# ESP32_with_USBC.net
KiCad netlist of a schematic drawn in Altium Designer
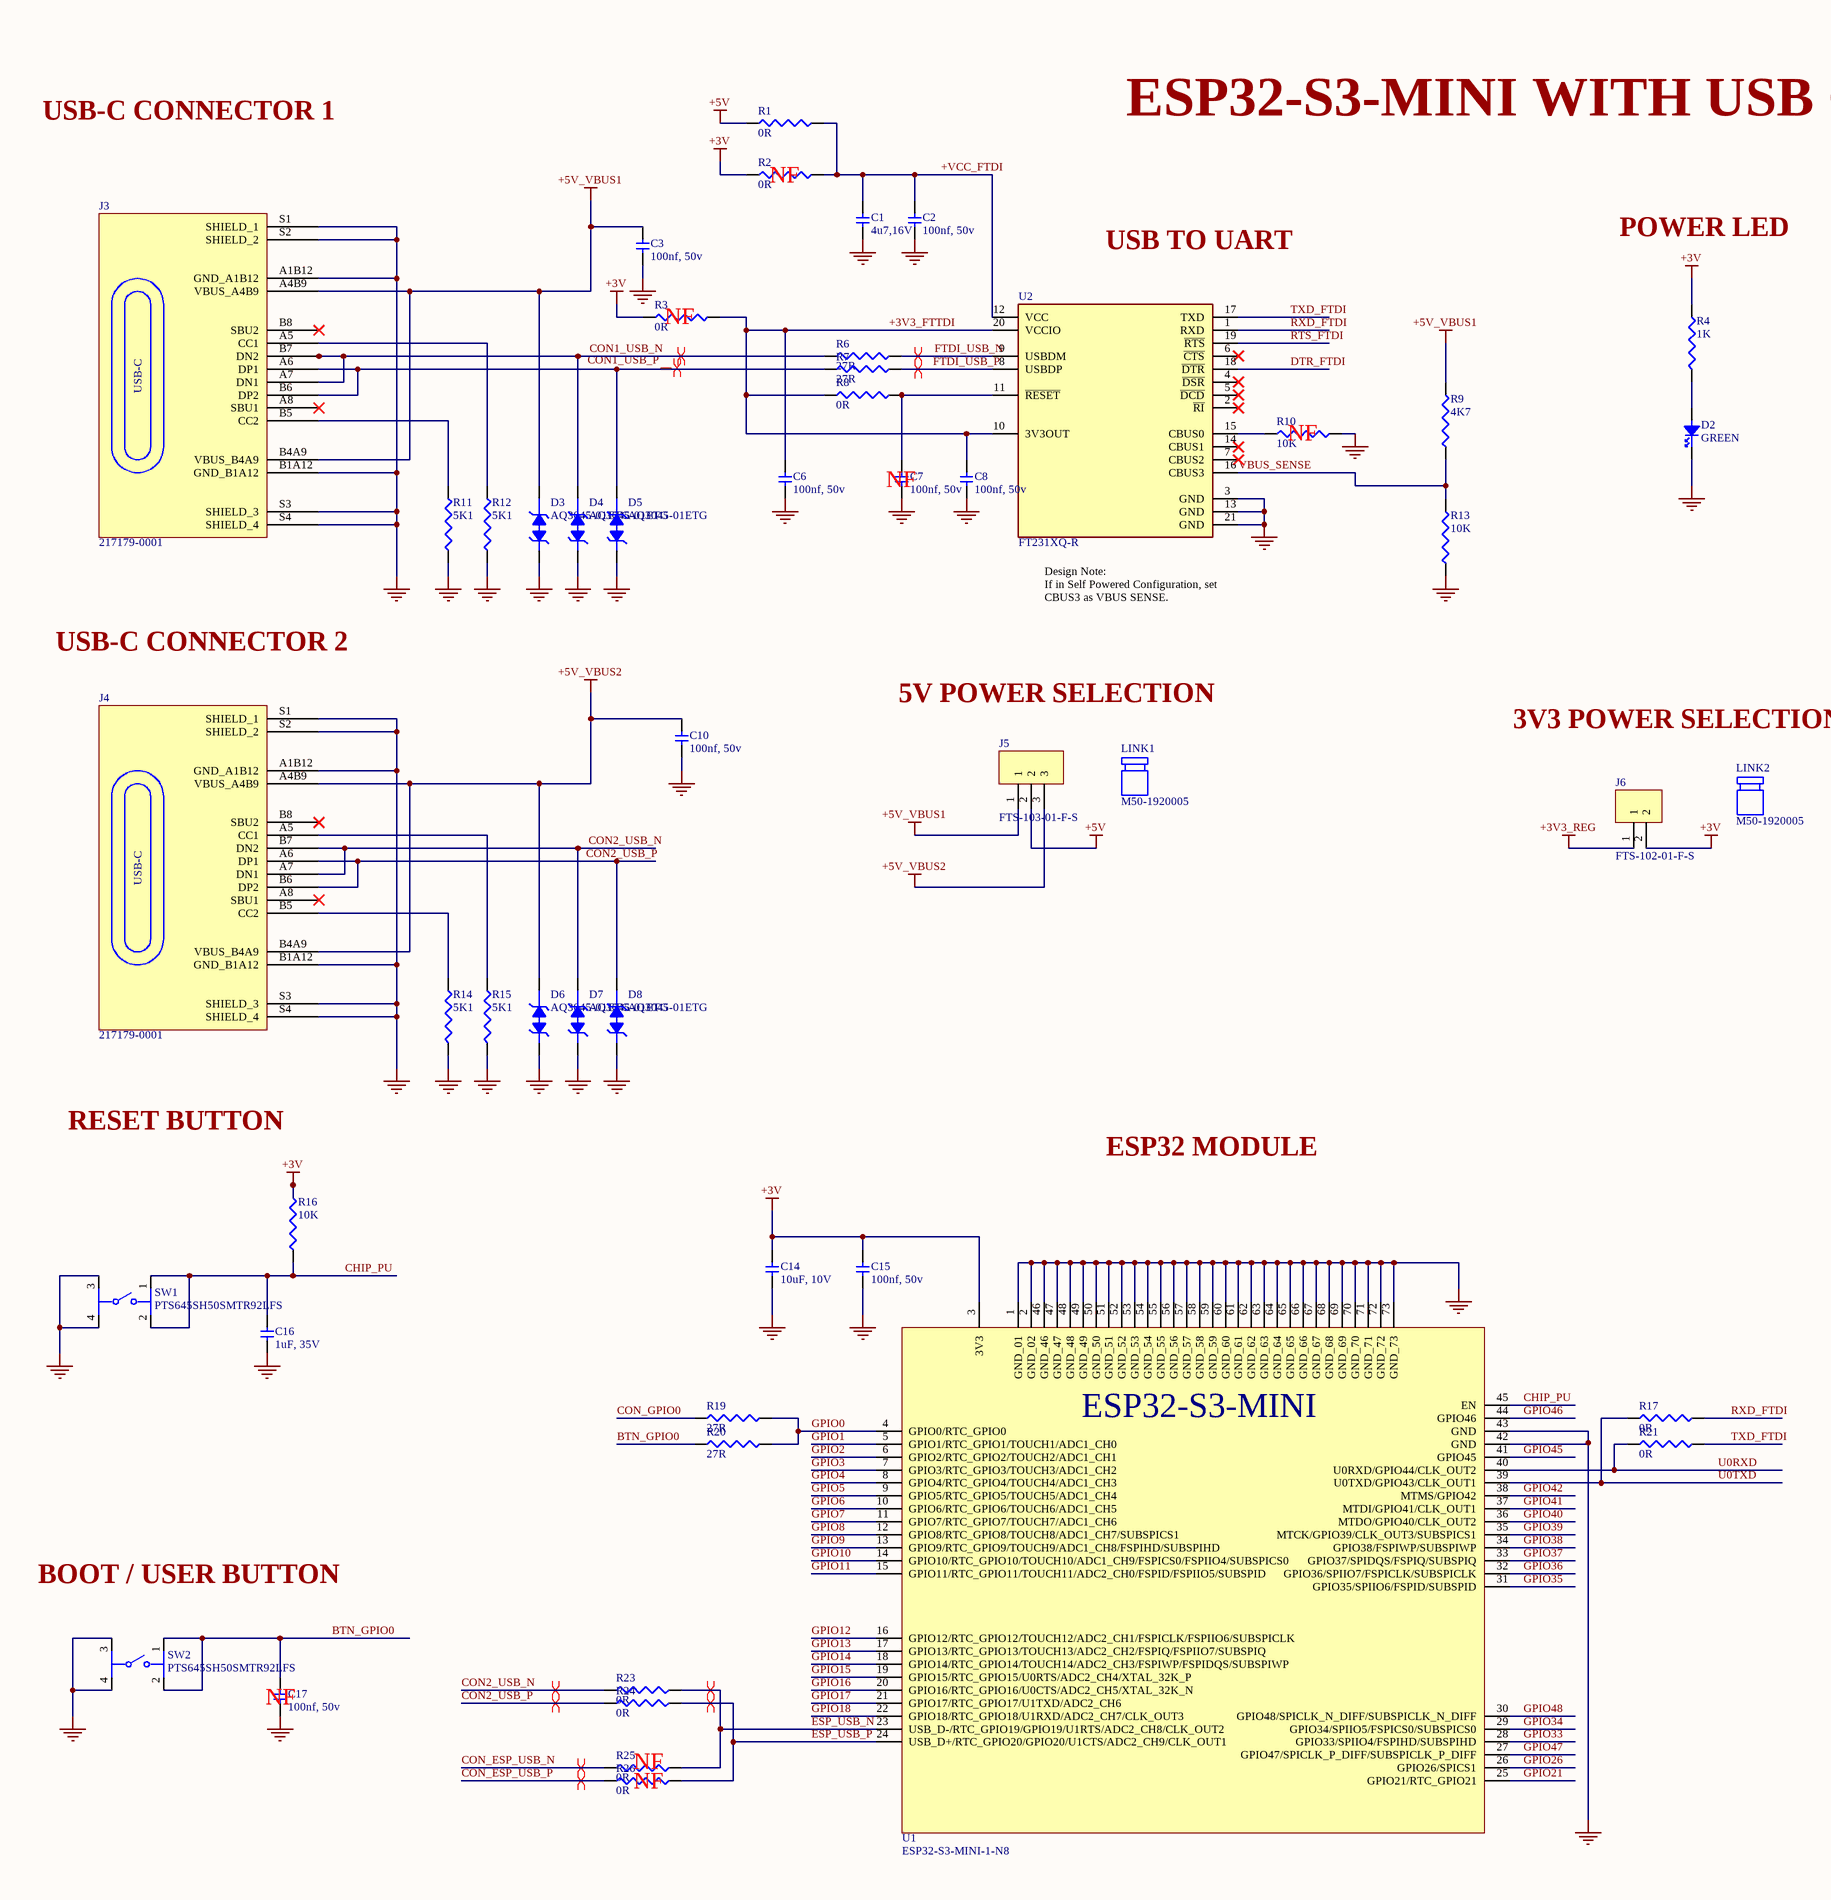
[diagram p0: ESP32 with USBC.SchDoc, left]
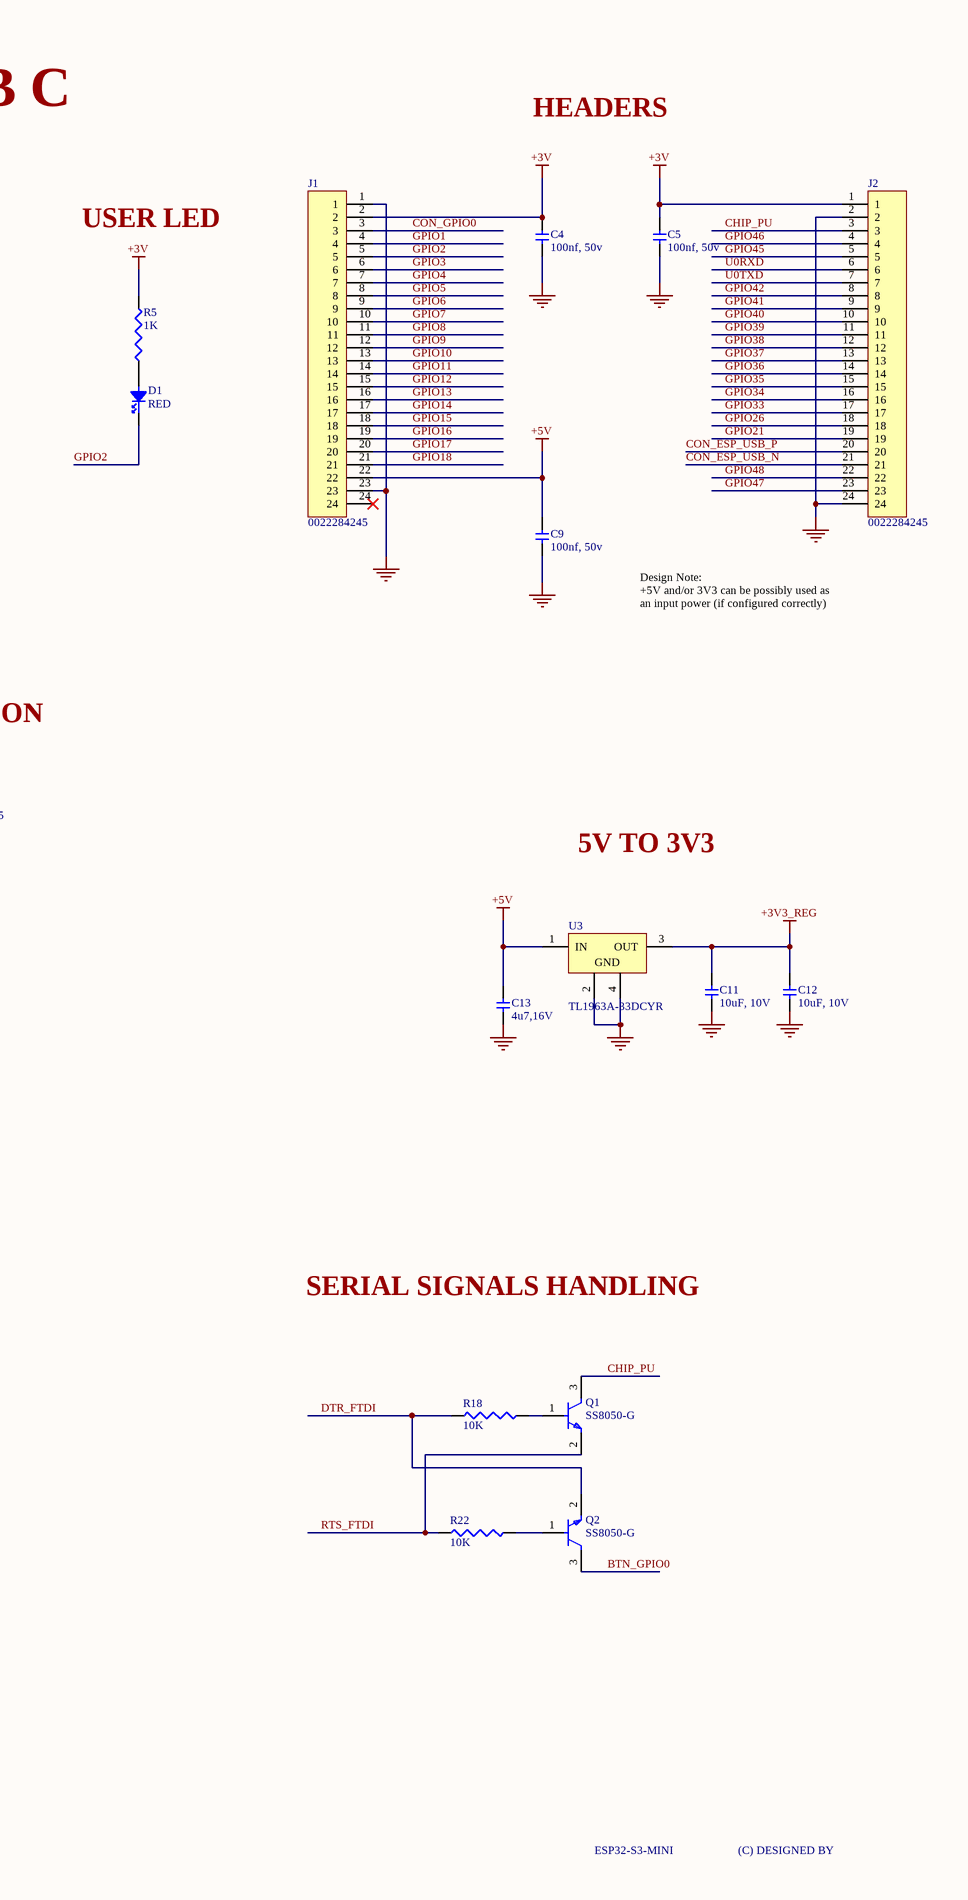
[diagram p1: ESP32 with USBC.SchDoc, right]

(export (version "E")
  (design (tool "Eeschema 10.0.6"))
  (components
    (comp (ref "C1")
      (value "4u7,16V")
      (footprint "CAPC1005X55N")
      (fields
        (field (name "MANUFACTURER") "Samsung")
        (field (name "MANUFACTURER PART NUMBER") "CL05A475MO5NUNC")
        (field (name "LCCS PART NUMBER") "C318563")
      )
      (libsource (lib "Schlib") (part "CL05A475MO5NUNC"))
    )
    (comp (ref "C2")
      (value "100nf, 50v")
      (footprint "CAPC1005X55N")
      (fields
        (field (name "MANUFACTURER") "Samsung")
        (field (name "MANUFACTURER PART NUMBER") "CL05B104KB54PNC")
        (field (name "LCCS PART NUMBER") "C307331")
      )
      (libsource (lib "Schlib") (part "CL05B104KB54PNC"))
    )
    (comp (ref "C3")
      (value "100nf, 50v")
      (footprint "CAPC1005X55N")
      (fields
        (field (name "MANUFACTURER") "Samsung")
        (field (name "MANUFACTURER PART NUMBER") "CL05B104KB54PNC")
        (field (name "LCCS PART NUMBER") "C307331")
      )
      (libsource (lib "Schlib") (part "CL05B104KB54PNC"))
    )
    (comp (ref "C4")
      (value "100nf, 50v")
      (footprint "CAPC1005X55N")
      (fields
        (field (name "MANUFACTURER") "Samsung")
        (field (name "MANUFACTURER PART NUMBER") "CL05B104KB54PNC")
        (field (name "LCCS PART NUMBER") "C307331")
      )
      (libsource (lib "Schlib") (part "CL05B104KB54PNC"))
    )
    (comp (ref "C5")
      (value "100nf, 50v")
      (footprint "CAPC1005X55N")
      (fields
        (field (name "MANUFACTURER") "Samsung")
        (field (name "MANUFACTURER PART NUMBER") "CL05B104KB54PNC")
        (field (name "LCCS PART NUMBER") "C307331")
      )
      (libsource (lib "Schlib") (part "CL05B104KB54PNC"))
    )
    (comp (ref "C6")
      (value "100nf, 50v")
      (footprint "CAPC1005X55N")
      (fields
        (field (name "MANUFACTURER") "Samsung")
        (field (name "MANUFACTURER PART NUMBER") "CL05B104KB54PNC")
        (field (name "LCCS PART NUMBER") "C307331")
      )
      (libsource (lib "Schlib") (part "CL05B104KB54PNC"))
    )
    (comp (ref "C7")
      (value "100nf, 50v")
      (footprint "CAPC1005X55N")
      (fields
        (field (name "MANUFACTURER") "Samsung")
        (field (name "MANUFACTURER PART NUMBER") "CL05B104KB54PNC")
        (field (name "LCCS PART NUMBER") "C307331")
      )
      (libsource (lib "Schlib") (part "CL05B104KB54PNC"))
    )
    (comp (ref "C8")
      (value "100nf, 50v")
      (footprint "CAPC1005X55N")
      (fields
        (field (name "MANUFACTURER") "Samsung")
        (field (name "MANUFACTURER PART NUMBER") "CL05B104KB54PNC")
        (field (name "LCCS PART NUMBER") "C307331")
      )
      (libsource (lib "Schlib") (part "CL05B104KB54PNC"))
    )
    (comp (ref "C9")
      (value "100nf, 50v")
      (footprint "CAPC1005X55N")
      (fields
        (field (name "MANUFACTURER") "Samsung")
        (field (name "MANUFACTURER PART NUMBER") "CL05B104KB54PNC")
        (field (name "LCCS PART NUMBER") "C307331")
      )
      (libsource (lib "Schlib") (part "CL05B104KB54PNC"))
    )
    (comp (ref "C10")
      (value "100nf, 50v")
      (footprint "CAPC1005X55N")
      (fields
        (field (name "MANUFACTURER") "Samsung")
        (field (name "MANUFACTURER PART NUMBER") "CL05B104KB54PNC")
        (field (name "LCCS PART NUMBER") "C307331")
      )
      (libsource (lib "Schlib") (part "CL05B104KB54PNC"))
    )
    (comp (ref "C11")
      (value "10uF, 10V")
      (footprint "CAPC1005X55N")
      (fields
        (field (name "MANUFACTURER") "Samsung")
        (field (name "MANUFACTURER PART NUMBER") "CL05A106MP8NUB8")
        (field (name "LCCS PART NUMBER") "C307415")
      )
      (libsource (lib "Schlib") (part "CL05A106MP8NUB8"))
    )
    (comp (ref "C12")
      (value "10uF, 10V")
      (footprint "CAPC1005X55N")
      (fields
        (field (name "MANUFACTURER") "Samsung")
        (field (name "MANUFACTURER PART NUMBER") "CL05A106MP8NUB8")
        (field (name "LCCS PART NUMBER") "C307415")
      )
      (libsource (lib "Schlib") (part "CL05A106MP8NUB8"))
    )
    (comp (ref "C13")
      (value "4u7,16V")
      (footprint "CAPC1005X55N")
      (fields
        (field (name "MANUFACTURER") "Samsung")
        (field (name "MANUFACTURER PART NUMBER") "CL05A475MO5NUNC")
        (field (name "LCCS PART NUMBER") "C318563")
      )
      (libsource (lib "Schlib") (part "CL05A475MO5NUNC"))
    )
    (comp (ref "C14")
      (value "10uF, 10V")
      (footprint "CAPC1005X55N")
      (fields
        (field (name "MANUFACTURER") "Samsung")
        (field (name "MANUFACTURER PART NUMBER") "CL05A106MP8NUB8")
        (field (name "LCCS PART NUMBER") "C307415")
      )
      (libsource (lib "Schlib") (part "CL05A106MP8NUB8"))
    )
    (comp (ref "C15")
      (value "100nf, 50v")
      (footprint "CAPC1005X55N")
      (fields
        (field (name "MANUFACTURER") "Samsung")
        (field (name "MANUFACTURER PART NUMBER") "CL05B104KB54PNC")
        (field (name "LCCS PART NUMBER") "C307331")
      )
      (libsource (lib "Schlib") (part "CL05B104KB54PNC"))
    )
    (comp (ref "C16")
      (value "1uF, 35V")
      (footprint "CAPC1005X55N")
      (fields
        (field (name "MANUFACTURER") "Samsung")
        (field (name "MANUFACTURER PART NUMBER") "CL05A105KL5NRNC")
        (field (name "LCCS PART NUMBER") "C307413")
      )
      (libsource (lib "Schlib") (part "CL05A105KL5NRNC"))
    )
    (comp (ref "C17")
      (value "100nf, 50v")
      (footprint "CAPC1005X55N")
      (fields
        (field (name "MANUFACTURER") "Samsung")
        (field (name "MANUFACTURER PART NUMBER") "CL05B104KB54PNC")
        (field (name "LCCS PART NUMBER") "C307331")
      )
      (libsource (lib "Schlib") (part "CL05B104KB54PNC"))
    )
    (comp (ref "D1")
      (value "RED")
      (footprint "LED0402R")
      (description "Single Color LED, Super Red, 0.5mm")
      (fields
        (field (name "MANUFACTURER") "Vishay")
        (field (name "MANUFACTURER PART NUMBER") "VLMS1500-GS08")
      )
      (libsource (lib "Schlib") (part "VLMS1500-GS08"))
    )
    (comp (ref "D2")
      (value "GREEN")
      (footprint "LED0402G")
      (description "Single Color LED, Yellow Green, 0.5mm")
      (fields
        (field (name "MANUFACTURER") "Vishay")
        (field (name "MANUFACTURER PART NUMBER") "VLMG1500-GS08")
      )
      (libsource (lib "Schlib") (part "VLMG1500-GS08"))
    )
    (comp (ref "D3")
      (value "AQ3045-01ETG")
      (footprint "SOD882")
      (description "Trans Voltage Suppressor Diode, 40W, 5.3V V(RWM), Bidirectional, 1 Element, Silicon, MO-236")
      (fields (field (name "MANUFACTURER") "Littelfuse") (field (name "LCCS PART NUMBER") "C3710326"))
      (libsource (lib "Schlib") (part "AQ3045-01ETG"))
    )
    (comp (ref "D4")
      (value "AQ3045-01ETG")
      (footprint "SOD882")
      (description "Trans Voltage Suppressor Diode, 40W, 5.3V V(RWM), Bidirectional, 1 Element, Silicon, MO-236")
      (fields (field (name "MANUFACTURER") "Littelfuse") (field (name "LCCS PART NUMBER") "C3710326"))
      (libsource (lib "Schlib") (part "AQ3045-01ETG"))
    )
    (comp (ref "D5")
      (value "AQ3045-01ETG")
      (footprint "SOD882")
      (description "Trans Voltage Suppressor Diode, 40W, 5.3V V(RWM), Bidirectional, 1 Element, Silicon, MO-236")
      (fields (field (name "MANUFACTURER") "Littelfuse") (field (name "LCCS PART NUMBER") "C3710326"))
      (libsource (lib "Schlib") (part "AQ3045-01ETG"))
    )
    (comp (ref "D6")
      (value "AQ3045-01ETG")
      (footprint "SOD882")
      (description "Trans Voltage Suppressor Diode, 40W, 5.3V V(RWM), Bidirectional, 1 Element, Silicon, MO-236")
      (fields (field (name "MANUFACTURER") "Littelfuse") (field (name "LCCS PART NUMBER") "C3710326"))
      (libsource (lib "Schlib") (part "AQ3045-01ETG"))
    )
    (comp (ref "D7")
      (value "AQ3045-01ETG")
      (footprint "SOD882")
      (description "Trans Voltage Suppressor Diode, 40W, 5.3V V(RWM), Bidirectional, 1 Element, Silicon, MO-236")
      (fields (field (name "MANUFACTURER") "Littelfuse") (field (name "LCCS PART NUMBER") "C3710326"))
      (libsource (lib "Schlib") (part "AQ3045-01ETG"))
    )
    (comp (ref "D8")
      (value "AQ3045-01ETG")
      (footprint "SOD882")
      (description "Trans Voltage Suppressor Diode, 40W, 5.3V V(RWM), Bidirectional, 1 Element, Silicon, MO-236")
      (fields (field (name "MANUFACTURER") "Littelfuse") (field (name "LCCS PART NUMBER") "C3710326"))
      (libsource (lib "Schlib") (part "AQ3045-01ETG"))
    )
    (comp (ref "J1")
      (value "0022284245")
      (footprint "HDR_1x24_2.54MM")
      (description "Board Connector, 24 Contact(s), 1 Row(s), Male, Straight, Solder Terminal")
      (fields (field (name "MANUFACTURER") "Molex") (field (name "LCCS PART NUMBER") "C7145888"))
      (libsource (lib "") (part "0022284245_1"))
    )
    (comp (ref "J2")
      (value "0022284245")
      (footprint "HDR_1x24_2.54MM")
      (description "Board Connector, 24 Contact(s), 1 Row(s), Male, Straight, Solder Terminal")
      (fields (field (name "MANUFACTURER") "Molex") (field (name "LCCS PART NUMBER") "C7145888"))
      (libsource (lib "Schlib") (part "0022284245"))
    )
    (comp (ref "J3")
      (value "217179-0001")
      (footprint "FP-2171790001-MFG")
      (description "USB Type C - Connector, Top-mount SMT, 16pos ¦ Molex Incorporated 217179-0001")
      (fields (field (name "MANUFACTURER") "Molex") (field (name "LCCS PART NUMBER") "C3179684"))
      (libsource (lib "Schlib") (part "217179-0001"))
    )
    (comp (ref "J4")
      (value "217179-0001")
      (footprint "FP-2171790001-MFG")
      (description "USB Type C - Connector, Top-mount SMT, 16pos ¦ Molex Incorporated 217179-0001")
      (fields (field (name "MANUFACTURER") "Molex") (field (name "LCCS PART NUMBER") "C3179684"))
      (libsource (lib "Schlib") (part "217179-0001"))
    )
    (comp (ref "J5")
      (value "FTS-103-01-F-S")
      (footprint "HDR_1X3_1.27MM")
      (description "Board Connector, 3 Contact(s), 1 Row(s), Male, Straight, Solder Terminal")
      (fields (field (name "MANUFACTURER") "Samtec") (field (name "LCCS PART NUMBER") "C3333578"))
      (libsource (lib "Schlib") (part "FTS-103-01-F-S"))
    )
    (comp (ref "J6")
      (value "FTS-102-01-F-S")
      (footprint "HDR_1X2_1.27MM")
      (description "Board Connector, 2 Contact(s), 1 Row(s), Male, Straight, Solder Terminal")
      (fields (field (name "MANUFACTURER") "Samtec") (field (name "LCCS PART NUMBER") "C6045317"))
      (libsource (lib "Schlib") (part "FTS-102-01-F-S"))
    )
    (comp (ref "LINK1")
      (value "M50-1920005")
      (description "Interconnection Device")
      (fields (field (name "MANUFACTURER") "Harwin") (field (name "LCCS PART NUMBER") "C6985646"))
      (libsource (lib "Schlib") (part "M50-1920005"))
    )
    (comp (ref "LINK2")
      (value "M50-1920005")
      (description "Interconnection Device")
      (fields (field (name "MANUFACTURER") "Harwin") (field (name "LCCS PART NUMBER") "C6985646"))
      (libsource (lib "Schlib") (part "M50-1920005"))
    )
    (comp (ref "Q1")
      (value "SS8050-G")
      (footprint "FP-SS8050-G-IPC_B")
      (description "Small Signal Bipolar Transistor, 1.5A I(C), 25V V(BR)CEO, 1-Element, NPN, Silicon")
      (fields (field (name "MANUFACTURER") "Comchip") (field (name "LCCS PART NUMBER") "C164886"))
      (libsource (lib "Schlib") (part "SS8050-G"))
    )
    (comp (ref "Q2")
      (value "SS8050-G")
      (footprint "FP-SS8050-G-IPC_B")
      (description "Small Signal Bipolar Transistor, 1.5A I(C), 25V V(BR)CEO, 1-Element, NPN, Silicon")
      (fields (field (name "MANUFACTURER") "Comchip") (field (name "LCCS PART NUMBER") "C164886"))
      (libsource (lib "Schlib") (part "SS8050-G"))
    )
    (comp (ref "R1")
      (value "0R")
      (footprint "RESC1005X37N")
      (description "Metal Glaze/thick Film, 0.0625W, 0ohm, Surface Mount, 0402")
      (fields
        (field (name "MANUFACTURER") "Yageo")
        (field (name "MANUFACTURER PART NUMBER") "RC0402JR-070RL")
      )
      (libsource (lib "Schlib") (part "RC0402JR-070RL"))
    )
    (comp (ref "R2")
      (value "0R")
      (footprint "RESC1005X37N")
      (description "Metal Glaze/thick Film, 0.0625W, 0ohm, Surface Mount, 0402")
      (fields
        (field (name "MANUFACTURER") "Yageo")
        (field (name "MANUFACTURER PART NUMBER") "RC0402JR-070RL")
      )
      (libsource (lib "Schlib") (part "RC0402JR-070RL"))
    )
    (comp (ref "R3")
      (value "0R")
      (footprint "RESC1005X37N")
      (description "Metal Glaze/thick Film, 0.0625W, 0ohm, Surface Mount, 0402")
      (fields
        (field (name "MANUFACTURER") "Yageo")
        (field (name "MANUFACTURER PART NUMBER") "RC0402JR-070RL")
      )
      (libsource (lib "Schlib") (part "RC0402JR-070RL"))
    )
    (comp (ref "R4")
      (value "1K")
      (footprint "RESC1005X37N")
      (fields
        (field (name "MANUFACTURER") "Yageo")
        (field (name "MANUFACTURER PART NUMBER") "RC0402FR-071KL")
        (field (name "TOLERANCE") "1%")
      )
      (libsource (lib "Schlib") (part "RC0402FR-071KL"))
    )
    (comp (ref "R5")
      (value "1K")
      (footprint "RESC1005X37N")
      (fields
        (field (name "MANUFACTURER") "Yageo")
        (field (name "MANUFACTURER PART NUMBER") "RC0402FR-071KL")
        (field (name "TOLERANCE") "1%")
      )
      (libsource (lib "Schlib") (part "RC0402FR-071KL"))
    )
    (comp (ref "R6")
      (value "27R")
      (footprint "RESC1005X37N")
      (fields
        (field (name "MANUFACTURER") "Yageo")
        (field (name "MANUFACTURER PART NUMBER") "RC0402FR-0727RL")
        (field (name "TOLERANCE") "1%")
      )
      (libsource (lib "Schlib") (part "RC0402FR-0727RL"))
    )
    (comp (ref "R7")
      (value "27R")
      (footprint "RESC1005X37N")
      (fields
        (field (name "MANUFACTURER") "Yageo")
        (field (name "MANUFACTURER PART NUMBER") "RC0402FR-0727RL")
        (field (name "TOLERANCE") "1%")
      )
      (libsource (lib "Schlib") (part "RC0402FR-0727RL"))
    )
    (comp (ref "R8")
      (value "0R")
      (footprint "RESC1005X37N")
      (description "Metal Glaze/thick Film, 0.0625W, 0ohm, Surface Mount, 0402")
      (fields
        (field (name "MANUFACTURER") "Yageo")
        (field (name "MANUFACTURER PART NUMBER") "RC0402JR-070RL")
      )
      (libsource (lib "Schlib") (part "RC0402JR-070RL"))
    )
    (comp (ref "R9")
      (value "4K7")
      (footprint "RESC1005X37N")
      (fields
        (field (name "MANUFACTURER") "Yageo")
        (field (name "MANUFACTURER PART NUMBER") "RC0402FR-074K7L")
        (field (name "TOLERANCE") "1%")
      )
      (libsource (lib "Schlib") (part "RC0402FR-074K7L"))
    )
    (comp (ref "R10")
      (value "10K")
      (footprint "RESC1005X37N")
      (fields
        (field (name "MANUFACTURER") "Yageo")
        (field (name "MANUFACTURER PART NUMBER") "AC0402FR-0710KL")
        (field (name "TOLERANCE") "1%")
      )
      (libsource (lib "Schlib") (part "AC0402FR-0710KL"))
    )
    (comp (ref "R11")
      (value "5K1")
      (footprint "RESC1005X37N")
      (fields
        (field (name "MANUFACTURER") "Yageo")
        (field (name "MANUFACTURER PART NUMBER") "AC0402FR-075K1L")
        (field (name "TOLERANCE") "1%")
      )
      (libsource (lib "Schlib") (part "AC0402FR-075K1L"))
    )
    (comp (ref "R12")
      (value "5K1")
      (footprint "RESC1005X37N")
      (fields
        (field (name "MANUFACTURER") "Yageo")
        (field (name "MANUFACTURER PART NUMBER") "AC0402FR-075K1L")
        (field (name "TOLERANCE") "1%")
      )
      (libsource (lib "Schlib") (part "AC0402FR-075K1L"))
    )
    (comp (ref "R13")
      (value "10K")
      (footprint "RESC1005X37N")
      (fields
        (field (name "MANUFACTURER") "Yageo")
        (field (name "MANUFACTURER PART NUMBER") "AC0402FR-0710KL")
        (field (name "TOLERANCE") "1%")
      )
      (libsource (lib "Schlib") (part "AC0402FR-0710KL"))
    )
    (comp (ref "R14")
      (value "5K1")
      (footprint "RESC1005X37N")
      (fields
        (field (name "MANUFACTURER") "Yageo")
        (field (name "MANUFACTURER PART NUMBER") "AC0402FR-075K1L")
        (field (name "TOLERANCE") "1%")
      )
      (libsource (lib "Schlib") (part "AC0402FR-075K1L"))
    )
    (comp (ref "R15")
      (value "5K1")
      (footprint "RESC1005X37N")
      (fields
        (field (name "MANUFACTURER") "Yageo")
        (field (name "MANUFACTURER PART NUMBER") "AC0402FR-075K1L")
        (field (name "TOLERANCE") "1%")
      )
      (libsource (lib "Schlib") (part "AC0402FR-075K1L"))
    )
    (comp (ref "R16")
      (value "10K")
      (footprint "RESC1005X37N")
      (fields
        (field (name "MANUFACTURER") "Yageo")
        (field (name "MANUFACTURER PART NUMBER") "AC0402FR-0710KL")
        (field (name "TOLERANCE") "1%")
      )
      (libsource (lib "Schlib") (part "AC0402FR-0710KL"))
    )
    (comp (ref "R17")
      (value "0R")
      (footprint "RESC1005X37N")
      (description "Metal Glaze/thick Film, 0.0625W, 0ohm, Surface Mount, 0402")
      (fields
        (field (name "MANUFACTURER") "Yageo")
        (field (name "MANUFACTURER PART NUMBER") "RC0402JR-070RL")
      )
      (libsource (lib "Schlib") (part "RC0402JR-070RL"))
    )
    (comp (ref "R18")
      (value "10K")
      (footprint "RESC1005X37N")
      (fields
        (field (name "MANUFACTURER") "Yageo")
        (field (name "MANUFACTURER PART NUMBER") "AC0402FR-0710KL")
        (field (name "TOLERANCE") "1%")
      )
      (libsource (lib "Schlib") (part "AC0402FR-0710KL"))
    )
    (comp (ref "R19")
      (value "27R")
      (footprint "RESC1005X37N")
      (fields
        (field (name "MANUFACTURER") "Yageo")
        (field (name "MANUFACTURER PART NUMBER") "RC0402FR-0727RL")
        (field (name "TOLERANCE") "1%")
      )
      (libsource (lib "Schlib") (part "RC0402FR-0727RL"))
    )
    (comp (ref "R20")
      (value "27R")
      (footprint "RESC1005X37N")
      (fields
        (field (name "MANUFACTURER") "Yageo")
        (field (name "MANUFACTURER PART NUMBER") "RC0402FR-0727RL")
        (field (name "TOLERANCE") "1%")
      )
      (libsource (lib "Schlib") (part "RC0402FR-0727RL"))
    )
    (comp (ref "R21")
      (value "0R")
      (footprint "RESC1005X37N")
      (description "Metal Glaze/thick Film, 0.0625W, 0ohm, Surface Mount, 0402")
      (fields
        (field (name "MANUFACTURER") "Yageo")
        (field (name "MANUFACTURER PART NUMBER") "RC0402JR-070RL")
      )
      (libsource (lib "Schlib") (part "RC0402JR-070RL"))
    )
    (comp (ref "R22")
      (value "10K")
      (footprint "RESC1005X37N")
      (fields
        (field (name "MANUFACTURER") "Yageo")
        (field (name "MANUFACTURER PART NUMBER") "AC0402FR-0710KL")
        (field (name "TOLERANCE") "1%")
      )
      (libsource (lib "Schlib") (part "AC0402FR-0710KL"))
    )
    (comp (ref "R23")
      (value "0R")
      (footprint "RESC1005X37N")
      (description "Metal Glaze/thick Film, 0.0625W, 0ohm, Surface Mount, 0402")
      (fields
        (field (name "MANUFACTURER") "Yageo")
        (field (name "MANUFACTURER PART NUMBER") "RC0402JR-070RL")
      )
      (libsource (lib "Schlib") (part "RC0402JR-070RL"))
    )
    (comp (ref "R24")
      (value "0R")
      (footprint "RESC1005X37N")
      (description "Metal Glaze/thick Film, 0.0625W, 0ohm, Surface Mount, 0402")
      (fields
        (field (name "MANUFACTURER") "Yageo")
        (field (name "MANUFACTURER PART NUMBER") "RC0402JR-070RL")
      )
      (libsource (lib "Schlib") (part "RC0402JR-070RL"))
    )
    (comp (ref "R25")
      (value "0R")
      (footprint "RESC1005X37N")
      (description "Metal Glaze/thick Film, 0.0625W, 0ohm, Surface Mount, 0402")
      (fields
        (field (name "MANUFACTURER") "Yageo")
        (field (name "MANUFACTURER PART NUMBER") "RC0402JR-070RL")
      )
      (libsource (lib "Schlib") (part "RC0402JR-070RL"))
    )
    (comp (ref "R26")
      (value "0R")
      (footprint "RESC1005X37N")
      (description "Metal Glaze/thick Film, 0.0625W, 0ohm, Surface Mount, 0402")
      (fields
        (field (name "MANUFACTURER") "Yageo")
        (field (name "MANUFACTURER PART NUMBER") "RC0402JR-070RL")
      )
      (libsource (lib "Schlib") (part "RC0402JR-070RL"))
    )
    (comp (ref "SW1")
      (value "PTS645SH50SMTR92LFS")
      (footprint "FP-PTS645SH50SMTR92LFS-MFG")
      (fields (field (name "MANUFACTURER") "ITT C&K") (field (name "LCCS PART NUMBER") "C221869"))
      (libsource (lib "Schlib") (part "PTS645SH50SMTR92LFS"))
    )
    (comp (ref "SW2")
      (value "PTS645SH50SMTR92LFS")
      (footprint "FP-PTS645SH50SMTR92LFS-MFG")
      (fields (field (name "MANUFACTURER") "ITT C&K") (field (name "LCCS PART NUMBER") "C221869"))
      (libsource (lib "Schlib") (part "PTS645SH50SMTR92LFS"))
    )
    (comp (ref "U1")
      (value "ESP32-S3-MINI-1-N8")
      (footprint "XCVR_ESP32-S3-MINI-1-N8")
      (description "SMD module, ESP32-S3FN8, 8 MB SPI flash, PCB antenna")
      (fields (field (name "MANUFACTURER") "Espressif Systems") (field (name "LCCS PART NUMBER") "C2913206"))
      (libsource (lib "Schlib") (part "ESP32-S3-MINI-1-N8"))
    )
    (comp (ref "U2")
      (value "FT231XQ-R")
      (footprint "FP-QFN-20-IPC_B")
      (description "Microprocessor Circuit, CMOS")
      (fields (field (name "MANUFACTURER") "FTDI") (field (name "LCCS PART NUMBER") "C132159"))
      (libsource (lib "Schlib") (part "FT231XQ-R"))
    )
    (comp (ref "U3")
      (value "TL1963A-33DCYR")
      (footprint "DCY0004A_N")
      (description "Fixed Positive LDO Regulator, 3.3V, 0.55V Dropout, BIPolar, PDSO4")
      (fields (field (name "MANUFACTURER") "Texas Instruments") (field (name "LCCS PART NUMBER") "C181262"))
      (libsource (lib "Schlib") (part "TL1963A-33DCYR"))
    )
  )
  (nets
    (net (code "1") (name "+3V") (class "Default")
      (node (ref "C14") (pin "2") (pinfunction "2_2") (pintype "passive"))
      (node (ref "C15") (pin "1") (pinfunction "1_1") (pintype "passive"))
      (node (ref "C4") (pin "1") (pinfunction "1_1") (pintype "passive"))
      (node (ref "C5") (pin "1") (pinfunction "1_1") (pintype "passive"))
      (node (ref "J1") (pin "2") (pinfunction "2_2") (pintype "passive"))
      (node (ref "J2") (pin "1") (pinfunction "1_1") (pintype "passive"))
      (node (ref "J6") (pin "2") (pinfunction "2_2") (pintype "passive"))
      (node (ref "R16") (pin "2") (pinfunction "2_2") (pintype "passive"))
      (node (ref "R2") (pin "1") (pinfunction "1_1") (pintype "passive"))
      (node (ref "R3") (pin "1") (pinfunction "1_1") (pintype "passive"))
      (node (ref "R4") (pin "2") (pinfunction "2_2") (pintype "passive"))
      (node (ref "R5") (pin "2") (pinfunction "2_2") (pintype "passive"))
      (node (ref "U1") (pin "3") (pinfunction "3V3_3") (pintype "passive"))
    )
    (net (code "2") (name "+3V3_REG") (class "Default")
      (node (ref "C11") (pin "2") (pinfunction "2_2") (pintype "passive"))
      (node (ref "C12") (pin "2") (pinfunction "2_2") (pintype "passive"))
      (node (ref "J6") (pin "1") (pinfunction "1_1") (pintype "passive"))
      (node (ref "U3") (pin "3") (pinfunction "OUT_3") (pintype "power_in"))
    )
    (net (code "3") (name "+5V") (class "Default")
      (node (ref "C13") (pin "2") (pinfunction "2_2") (pintype "passive"))
      (node (ref "C9") (pin "1") (pinfunction "1_1") (pintype "passive"))
      (node (ref "J1") (pin "22") (pinfunction "22_22") (pintype "passive"))
      (node (ref "J5") (pin "2") (pinfunction "2_2") (pintype "passive"))
      (node (ref "R1") (pin "1") (pinfunction "1_1") (pintype "passive"))
      (node (ref "U3") (pin "1") (pinfunction "IN_1") (pintype "power_in"))
    )
    (net (code "4") (name "+5V_VBUS1") (class "Default")
      (node (ref "C3") (pin "1") (pinfunction "1_1") (pintype "passive"))
      (node (ref "D3") (pin "2") (pinfunction "2_2") (pintype "passive"))
      (node (ref "J3") (pin "A4B9") (pinfunction "VBUS_A4B9_A4B9") (pintype "passive"))
      (node (ref "J3") (pin "B4A9") (pinfunction "VBUS_B4A9_B4A9") (pintype "passive"))
      (node (ref "J5") (pin "1") (pinfunction "1_1") (pintype "passive"))
      (node (ref "R9") (pin "2") (pinfunction "2_2") (pintype "passive"))
    )
    (net (code "5") (name "+5V_VBUS2") (class "Default")
      (node (ref "C10") (pin "1") (pinfunction "1_1") (pintype "passive"))
      (node (ref "D6") (pin "2") (pinfunction "2_2") (pintype "passive"))
      (node (ref "J4") (pin "A4B9") (pinfunction "VBUS_A4B9_A4B9") (pintype "passive"))
      (node (ref "J4") (pin "B4A9") (pinfunction "VBUS_B4A9_B4A9") (pintype "passive"))
      (node (ref "J5") (pin "3") (pinfunction "3_3") (pintype "passive"))
    )
    (net (code "6") (name "/+3V3_FTTDI") (class "Default")
      (node (ref "C6") (pin "1") (pinfunction "1_1") (pintype "passive"))
      (node (ref "C8") (pin "1") (pinfunction "1_1") (pintype "passive"))
      (node (ref "R3") (pin "2") (pinfunction "2_2") (pintype "passive"))
      (node (ref "R8") (pin "1") (pinfunction "1_1") (pintype "passive"))
      (node (ref "U2") (pin "10") (pinfunction "3V3OUT_10") (pintype "passive"))
      (node (ref "U2") (pin "20") (pinfunction "VCCIO_20") (pintype "passive"))
    )
    (net (code "7") (name "/+VCC_FTDI") (class "Default")
      (node (ref "C1") (pin "2") (pinfunction "2_2") (pintype "passive"))
      (node (ref "C2") (pin "1") (pinfunction "1_1") (pintype "passive"))
      (node (ref "R1") (pin "2") (pinfunction "2_2") (pintype "passive"))
      (node (ref "R2") (pin "2") (pinfunction "2_2") (pintype "passive"))
      (node (ref "U2") (pin "12") (pinfunction "VCC_12") (pintype "passive"))
    )
    (net (code "8") (name "/BTN_GPIO0") (class "Default")
      (node (ref "C17") (pin "1") (pinfunction "1_1") (pintype "passive"))
      (node (ref "Q2") (pin "3") (pinfunction "C_3") (pintype "passive"))
      (node (ref "R20") (pin "1") (pinfunction "1_1") (pintype "passive"))
      (node (ref "SW2") (pin "1") (pinfunction "1_1") (pintype "passive"))
      (node (ref "SW2") (pin "2") (pinfunction "2_2") (pintype "passive"))
    )
    (net (code "9") (name "/CHIP_PU") (class "Default")
      (node (ref "C16") (pin "2") (pinfunction "2_2") (pintype "passive"))
      (node (ref "J2") (pin "3") (pinfunction "3_3") (pintype "passive"))
      (node (ref "Q1") (pin "3") (pinfunction "C_3") (pintype "passive"))
      (node (ref "R16") (pin "1") (pinfunction "1_1") (pintype "passive"))
      (node (ref "SW1") (pin "1") (pinfunction "1_1") (pintype "passive"))
      (node (ref "SW1") (pin "2") (pinfunction "2_2") (pintype "passive"))
      (node (ref "U1") (pin "45") (pinfunction "EN_45") (pintype "passive"))
    )
    (net (code "10") (name "/CON1_USB_N") (class "Default")
      (node (ref "D4") (pin "2") (pinfunction "2_2") (pintype "passive"))
      (node (ref "J3") (pin "A7") (pinfunction "DN1_A7") (pintype "passive"))
      (node (ref "J3") (pin "B7") (pinfunction "DN2_B7") (pintype "passive"))
      (node (ref "R6") (pin "1") (pinfunction "1_1") (pintype "passive"))
    )
    (net (code "12") (name "/CON2_USB_N") (class "Default")
      (node (ref "D7") (pin "2") (pinfunction "2_2") (pintype "passive"))
      (node (ref "J4") (pin "A7") (pinfunction "DN1_A7") (pintype "passive"))
      (node (ref "J4") (pin "B7") (pinfunction "DN2_B7") (pintype "passive"))
      (node (ref "R23") (pin "1") (pinfunction "1_1") (pintype "passive"))
    )
    (net (code "13") (name "/CON2_USB_P") (class "Default")
      (node (ref "D8") (pin "2") (pinfunction "2_2") (pintype "passive"))
      (node (ref "J4") (pin "A6") (pinfunction "DP1_A6") (pintype "passive"))
      (node (ref "J4") (pin "B6") (pinfunction "DP2_B6") (pintype "passive"))
      (node (ref "R24") (pin "1") (pinfunction "1_1") (pintype "passive"))
    )
    (net (code "14") (name "/CON_ESP_USB_N") (class "Default")
      (node (ref "J2") (pin "21") (pinfunction "21_21") (pintype "passive"))
      (node (ref "R25") (pin "1") (pinfunction "1_1") (pintype "passive"))
    )
    (net (code "15") (name "/CON_ESP_USB_P") (class "Default")
      (node (ref "J2") (pin "20") (pinfunction "20_20") (pintype "passive"))
      (node (ref "R26") (pin "1") (pinfunction "1_1") (pintype "passive"))
    )
    (net (code "16") (name "/CON_GPIO0") (class "Default")
      (node (ref "J1") (pin "3") (pinfunction "3_3") (pintype "passive"))
      (node (ref "R19") (pin "1") (pinfunction "1_1") (pintype "passive"))
    )
    (net (code "17") (name "/DTR_FTDI") (class "Default")
      (node (ref "Q2") (pin "2") (pinfunction "E_2") (pintype "passive"))
      (node (ref "R18") (pin "2") (pinfunction "2_2") (pintype "passive"))
      (node (ref "U2") (pin "18") (pinfunction "~{DTR}_18") (pintype "passive"))
    )
    (net (code "18") (name "/ESP_USB_N") (class "Default")
      (node (ref "R23") (pin "2") (pinfunction "2_2") (pintype "passive"))
      (node (ref "R25") (pin "2") (pinfunction "2_2") (pintype "passive"))
      (node (ref "U1") (pin "23") (pinfunction "USB_D-/RTC_GPIO19/GPIO19/U1RTS/ADC2_CH8/CLK_OUT2_23") (pintype "passive"))
    )
    (net (code "19") (name "/ESP_USB_P") (class "Default")
      (node (ref "R24") (pin "2") (pinfunction "2_2") (pintype "passive"))
      (node (ref "R26") (pin "2") (pinfunction "2_2") (pintype "passive"))
      (node (ref "U1") (pin "24") (pinfunction "USB_D+/RTC_GPIO20/GPIO20/U1CTS/ADC2_CH9/CLK_OUT1_24") (pintype "passive"))
    )
    (net (code "20") (name "/FTDI_USB_N") (class "Default")
      (node (ref "R6") (pin "2") (pinfunction "2_2") (pintype "passive"))
      (node (ref "U2") (pin "9") (pinfunction "USBDM_9") (pintype "passive"))
    )
    (net (code "21") (name "/FTDI_USB_P") (class "Default")
      (node (ref "R7") (pin "2") (pinfunction "2_2") (pintype "passive"))
      (node (ref "U2") (pin "8") (pinfunction "USBDP_8") (pintype "passive"))
    )
    (net (code "22") (name "/GPIO0") (class "Default")
      (node (ref "R19") (pin "2") (pinfunction "2_2") (pintype "passive"))
      (node (ref "R20") (pin "2") (pinfunction "2_2") (pintype "passive"))
      (node (ref "U1") (pin "4") (pinfunction "GPIO0/RTC_GPIO0_4") (pintype "passive"))
    )
    (net (code "23") (name "/GPIO1") (class "Default")
      (node (ref "J1") (pin "4") (pinfunction "4_4") (pintype "passive"))
      (node (ref "U1") (pin "5") (pinfunction "GPIO1/RTC_GPIO1/TOUCH1/ADC1_CH0_5") (pintype "passive"))
    )
    (net (code "24") (name "/GPIO2") (class "Default")
      (node (ref "D1") (pin "1") (pinfunction "1_1") (pintype "passive"))
      (node (ref "J1") (pin "5") (pinfunction "5_5") (pintype "passive"))
      (node (ref "U1") (pin "6") (pinfunction "GPIO2/RTC_GPIO2/TOUCH2/ADC1_CH1_6") (pintype "passive"))
    )
    (net (code "25") (name "/GPIO3") (class "Default")
      (node (ref "J1") (pin "6") (pinfunction "6_6") (pintype "passive"))
      (node (ref "U1") (pin "7") (pinfunction "GPIO3/RTC_GPIO3/TOUCH3/ADC1_CH2_7") (pintype "passive"))
    )
    (net (code "26") (name "/GPIO4") (class "Default")
      (node (ref "J1") (pin "7") (pinfunction "7_7") (pintype "passive"))
      (node (ref "U1") (pin "8") (pinfunction "GPIO4/RTC_GPIO4/TOUCH4/ADC1_CH3_8") (pintype "passive"))
    )
    (net (code "27") (name "/GPIO5") (class "Default")
      (node (ref "J1") (pin "8") (pinfunction "8_8") (pintype "passive"))
      (node (ref "U1") (pin "9") (pinfunction "GPIO5/RTC_GPIO5/TOUCH5/ADC1_CH4_9") (pintype "passive"))
    )
    (net (code "28") (name "/GPIO6") (class "Default")
      (node (ref "J1") (pin "9") (pinfunction "9_9") (pintype "passive"))
      (node (ref "U1") (pin "10") (pinfunction "GPIO6/RTC_GPIO6/TOUCH6/ADC1_CH5_10") (pintype "passive"))
    )
    (net (code "29") (name "/GPIO7") (class "Default")
      (node (ref "J1") (pin "10") (pinfunction "10_10") (pintype "passive"))
      (node (ref "U1") (pin "11") (pinfunction "GPIO7/RTC_GPIO7/TOUCH7/ADC1_CH6_11") (pintype "passive"))
    )
    (net (code "30") (name "/GPIO8") (class "Default")
      (node (ref "J1") (pin "11") (pinfunction "11_11") (pintype "passive"))
      (node (ref "U1") (pin "12") (pinfunction "GPIO8/RTC_GPIO8/TOUCH8/ADC1_CH7/SUBSPICS1_12") (pintype "passive"))
    )
    (net (code "31") (name "/GPIO9") (class "Default")
      (node (ref "J1") (pin "12") (pinfunction "12_12") (pintype "passive"))
      (node (ref "U1") (pin "13") (pinfunction "GPIO9/RTC_GPIO9/TOUCH9/ADC1_CH8/FSPIHD/SUBSPIHD_13") (pintype "passive"))
    )
    (net (code "32") (name "/GPIO10") (class "Default")
      (node (ref "J1") (pin "13") (pinfunction "13_13") (pintype "passive"))
      (node (ref "U1") (pin "14") (pinfunction "GPIO10/RTC_GPIO10/TOUCH10/ADC1_CH9/FSPICS0/FSPIIO4/SUBSPICS0_14") (pintype "passive"))
    )
    (net (code "33") (name "/GPIO11") (class "Default")
      (node (ref "J1") (pin "14") (pinfunction "14_14") (pintype "passive"))
      (node (ref "U1") (pin "15") (pinfunction "GPIO11/RTC_GPIO11/TOUCH11/ADC2_CH0/FSPID/FSPIIO5/SUBSPID_15") (pintype "passive"))
    )
    (net (code "34") (name "/GPIO12") (class "Default")
      (node (ref "J1") (pin "15") (pinfunction "15_15") (pintype "passive"))
      (node (ref "U1") (pin "16") (pinfunction "GPIO12/RTC_GPIO12/TOUCH12/ADC2_CH1/FSPICLK/FSPIIO6/SUBSPICLK_16") (pintype "passive"))
    )
    (net (code "35") (name "/GPIO13") (class "Default")
      (node (ref "J1") (pin "16") (pinfunction "16_16") (pintype "passive"))
      (node (ref "U1") (pin "17") (pinfunction "GPIO13/RTC_GPIO13/TOUCH13/ADC2_CH2/FSPIQ/FSPIIO7/SUBSPIQ_17") (pintype "passive"))
    )
    (net (code "36") (name "/GPIO14") (class "Default")
      (node (ref "J1") (pin "17") (pinfunction "17_17") (pintype "passive"))
      (node (ref "U1") (pin "18") (pinfunction "GPIO14/RTC_GPIO14/TOUCH14/ADC2_CH3/FSPIWP/FSPIDQS/SUBSPIWP_18") (pintype "passive"))
    )
    (net (code "37") (name "/GPIO15") (class "Default")
      (node (ref "J1") (pin "18") (pinfunction "18_18") (pintype "passive"))
      (node (ref "U1") (pin "19") (pinfunction "GPIO15/RTC_GPIO15/U0RTS/ADC2_CH4/XTAL_32K_P_19") (pintype "passive"))
    )
    (net (code "38") (name "/GPIO16") (class "Default")
      (node (ref "J1") (pin "19") (pinfunction "19_19") (pintype "passive"))
      (node (ref "U1") (pin "20") (pinfunction "GPIO16/RTC_GPIO16/U0CTS/ADC2_CH5/XTAL_32K_N_20") (pintype "passive"))
    )
    (net (code "39") (name "/GPIO17") (class "Default")
      (node (ref "J1") (pin "20") (pinfunction "20_20") (pintype "passive"))
      (node (ref "U1") (pin "21") (pinfunction "GPIO17/RTC_GPIO17/U1TXD/ADC2_CH6_21") (pintype "passive"))
    )
    (net (code "40") (name "/GPIO18") (class "Default")
      (node (ref "J1") (pin "21") (pinfunction "21_21") (pintype "passive"))
      (node (ref "U1") (pin "22") (pinfunction "GPIO18/RTC_GPIO18/U1RXD/ADC2_CH7/CLK_OUT3_22") (pintype "passive"))
    )
    (net (code "41") (name "/GPIO21") (class "Default")
      (node (ref "J2") (pin "19") (pinfunction "19_19") (pintype "passive"))
      (node (ref "U1") (pin "25") (pinfunction "GPIO21/RTC_GPIO21_25") (pintype "passive"))
    )
    (net (code "42") (name "/GPIO26") (class "Default")
      (node (ref "J2") (pin "18") (pinfunction "18_18") (pintype "passive"))
      (node (ref "U1") (pin "26") (pinfunction "GPIO26/SPICS1_26") (pintype "passive"))
    )
    (net (code "43") (name "/GPIO33") (class "Default")
      (node (ref "J2") (pin "17") (pinfunction "17_17") (pintype "passive"))
      (node (ref "U1") (pin "28") (pinfunction "GPIO33/SPIIO4/FSPIHD/SUBSPIHD_28") (pintype "passive"))
    )
    (net (code "44") (name "/GPIO34") (class "Default")
      (node (ref "J2") (pin "16") (pinfunction "16_16") (pintype "passive"))
      (node (ref "U1") (pin "29") (pinfunction "GPIO34/SPIIO5/FSPICS0/SUBSPICS0_29") (pintype "passive"))
    )
    (net (code "45") (name "/GPIO35") (class "Default")
      (node (ref "J2") (pin "15") (pinfunction "15_15") (pintype "passive"))
      (node (ref "U1") (pin "31") (pinfunction "GPIO35/SPIIO6/FSPID/SUBSPID_31") (pintype "passive"))
    )
    (net (code "46") (name "/GPIO36") (class "Default")
      (node (ref "J2") (pin "14") (pinfunction "14_14") (pintype "passive"))
      (node (ref "U1") (pin "32") (pinfunction "GPIO36/SPIIO7/FSPICLK/SUBSPICLK_32") (pintype "passive"))
    )
    (net (code "47") (name "/GPIO37") (class "Default")
      (node (ref "J2") (pin "13") (pinfunction "13_13") (pintype "passive"))
      (node (ref "U1") (pin "33") (pinfunction "GPIO37/SPIDQS/FSPIQ/SUBSPIQ_33") (pintype "passive"))
    )
    (net (code "48") (name "/GPIO38") (class "Default")
      (node (ref "J2") (pin "12") (pinfunction "12_12") (pintype "passive"))
      (node (ref "U1") (pin "34") (pinfunction "GPIO38/FSPIWP/SUBSPIWP_34") (pintype "passive"))
    )
    (net (code "49") (name "/GPIO39") (class "Default")
      (node (ref "J2") (pin "11") (pinfunction "11_11") (pintype "passive"))
      (node (ref "U1") (pin "35") (pinfunction "MTCK/GPIO39/CLK_OUT3/SUBSPICS1_35") (pintype "passive"))
    )
    (net (code "50") (name "/GPIO40") (class "Default")
      (node (ref "J2") (pin "10") (pinfunction "10_10") (pintype "passive"))
      (node (ref "U1") (pin "36") (pinfunction "MTDO/GPIO40/CLK_OUT2_36") (pintype "passive"))
    )
    (net (code "51") (name "/GPIO41") (class "Default")
      (node (ref "J2") (pin "9") (pinfunction "9_9") (pintype "passive"))
      (node (ref "U1") (pin "37") (pinfunction "MTDI/GPIO41/CLK_OUT1_37") (pintype "passive"))
    )
    (net (code "52") (name "/GPIO42") (class "Default")
      (node (ref "J2") (pin "8") (pinfunction "8_8") (pintype "passive"))
      (node (ref "U1") (pin "38") (pinfunction "MTMS/GPIO42_38") (pintype "passive"))
    )
    (net (code "53") (name "/GPIO45") (class "Default")
      (node (ref "J2") (pin "5") (pinfunction "5_5") (pintype "passive"))
      (node (ref "U1") (pin "41") (pinfunction "GPIO45_41") (pintype "passive"))
    )
    (net (code "54") (name "/GPIO46") (class "Default")
      (node (ref "J2") (pin "4") (pinfunction "4_4") (pintype "passive"))
      (node (ref "U1") (pin "44") (pinfunction "GPIO46_44") (pintype "passive"))
    )
    (net (code "55") (name "/GPIO47") (class "Default")
      (node (ref "J2") (pin "23") (pinfunction "23_23") (pintype "passive"))
      (node (ref "U1") (pin "27") (pinfunction "GPIO47/SPICLK_P_DIFF/SUBSPICLK_P_DIFF_27") (pintype "passive"))
    )
    (net (code "56") (name "/GPIO48") (class "Default")
      (node (ref "J2") (pin "22") (pinfunction "22_22") (pintype "passive"))
      (node (ref "U1") (pin "30") (pinfunction "GPIO48/SPICLK_N_DIFF/SUBSPICLK_N_DIFF_30") (pintype "passive"))
    )
    (net (code "57") (name "/RTS_FTDI") (class "Default")
      (node (ref "Q1") (pin "2") (pinfunction "E_2") (pintype "passive"))
      (node (ref "R22") (pin "2") (pinfunction "2_2") (pintype "passive"))
      (node (ref "U2") (pin "19") (pinfunction "~{RTS}_19") (pintype "passive"))
    )
    (net (code "58") (name "/RXD_FTDI") (class "Default")
      (node (ref "R17") (pin "2") (pinfunction "2_2") (pintype "passive"))
      (node (ref "U2") (pin "1") (pinfunction "RXD_1") (pintype "passive"))
    )
    (net (code "59") (name "/TXD_FTDI") (class "Default")
      (node (ref "R21") (pin "2") (pinfunction "2_2") (pintype "passive"))
      (node (ref "U2") (pin "17") (pinfunction "TXD_17") (pintype "passive"))
    )
    (net (code "60") (name "/U0RXD") (class "Default")
      (node (ref "J2") (pin "6") (pinfunction "6_6") (pintype "passive"))
      (node (ref "R21") (pin "1") (pinfunction "1_1") (pintype "passive"))
      (node (ref "U1") (pin "40") (pinfunction "U0RXD/GPIO44/CLK_OUT2_40") (pintype "passive"))
    )
    (net (code "61") (name "/U0TXD") (class "Default")
      (node (ref "J2") (pin "7") (pinfunction "7_7") (pintype "passive"))
      (node (ref "R17") (pin "1") (pinfunction "1_1") (pintype "passive"))
      (node (ref "U1") (pin "39") (pinfunction "U0TXD/GPIO43/CLK_OUT1_39") (pintype "passive"))
    )
    (net (code "62") (name "/VBUS_SENSE") (class "Default")
      (node (ref "R13") (pin "2") (pinfunction "2_2") (pintype "passive"))
      (node (ref "R9") (pin "1") (pinfunction "1_1") (pintype "passive"))
      (node (ref "U2") (pin "16") (pinfunction "CBUS3_16") (pintype "passive"))
    )
    (net (code "63") (name "GND") (class "Default")
      (node (ref "C1") (pin "1") (pinfunction "1_1") (pintype "passive"))
      (node (ref "C10") (pin "2") (pinfunction "2_2") (pintype "passive"))
      (node (ref "C11") (pin "1") (pinfunction "1_1") (pintype "passive"))
      (node (ref "C12") (pin "1") (pinfunction "1_1") (pintype "passive"))
      (node (ref "C13") (pin "1") (pinfunction "1_1") (pintype "passive"))
      (node (ref "C14") (pin "1") (pinfunction "1_1") (pintype "passive"))
      (node (ref "C15") (pin "2") (pinfunction "2_2") (pintype "passive"))
      (node (ref "C16") (pin "1") (pinfunction "1_1") (pintype "passive"))
      (node (ref "C17") (pin "2") (pinfunction "2_2") (pintype "passive"))
      (node (ref "C2") (pin "2") (pinfunction "2_2") (pintype "passive"))
      (node (ref "C3") (pin "2") (pinfunction "2_2") (pintype "passive"))
      (node (ref "C4") (pin "2") (pinfunction "2_2") (pintype "passive"))
      (node (ref "C5") (pin "2") (pinfunction "2_2") (pintype "passive"))
      (node (ref "C6") (pin "2") (pinfunction "2_2") (pintype "passive"))
      (node (ref "C7") (pin "2") (pinfunction "2_2") (pintype "passive"))
      (node (ref "C8") (pin "2") (pinfunction "2_2") (pintype "passive"))
      (node (ref "C9") (pin "2") (pinfunction "2_2") (pintype "passive"))
      (node (ref "D2") (pin "1") (pinfunction "1_1") (pintype "passive"))
      (node (ref "D3") (pin "1") (pinfunction "1_1") (pintype "passive"))
      (node (ref "D4") (pin "1") (pinfunction "1_1") (pintype "passive"))
      (node (ref "D5") (pin "1") (pinfunction "1_1") (pintype "passive"))
      (node (ref "D6") (pin "1") (pinfunction "1_1") (pintype "passive"))
      (node (ref "D7") (pin "1") (pinfunction "1_1") (pintype "passive"))
      (node (ref "D8") (pin "1") (pinfunction "1_1") (pintype "passive"))
      (node (ref "J1") (pin "1") (pinfunction "1_1") (pintype "passive"))
      (node (ref "J1") (pin "23") (pinfunction "23_23") (pintype "passive"))
      (node (ref "J2") (pin "2") (pinfunction "2_2") (pintype "passive"))
      (node (ref "J2") (pin "24") (pinfunction "24_24") (pintype "passive"))
      (node (ref "J3") (pin "A1B12") (pinfunction "GND_A1B12_A1B12") (pintype "passive"))
      (node (ref "J3") (pin "B1A12") (pinfunction "GND_B1A12_B1A12") (pintype "passive"))
      (node (ref "J3") (pin "S1") (pinfunction "SHIELD_1_S1") (pintype "passive"))
      (node (ref "J3") (pin "S2") (pinfunction "SHIELD_2_S2") (pintype "passive"))
      (node (ref "J3") (pin "S3") (pinfunction "SHIELD_3_S3") (pintype "passive"))
      (node (ref "J3") (pin "S4") (pinfunction "SHIELD_4_S4") (pintype "passive"))
      (node (ref "J4") (pin "A1B12") (pinfunction "GND_A1B12_A1B12") (pintype "passive"))
      (node (ref "J4") (pin "B1A12") (pinfunction "GND_B1A12_B1A12") (pintype "passive"))
      (node (ref "J4") (pin "S1") (pinfunction "SHIELD_1_S1") (pintype "passive"))
      (node (ref "J4") (pin "S2") (pinfunction "SHIELD_2_S2") (pintype "passive"))
      (node (ref "J4") (pin "S3") (pinfunction "SHIELD_3_S3") (pintype "passive"))
      (node (ref "J4") (pin "S4") (pinfunction "SHIELD_4_S4") (pintype "passive"))
      (node (ref "R10") (pin "2") (pinfunction "2_2") (pintype "passive"))
      (node (ref "R11") (pin "1") (pinfunction "1_1") (pintype "passive"))
      (node (ref "R12") (pin "1") (pinfunction "1_1") (pintype "passive"))
      (node (ref "R13") (pin "1") (pinfunction "1_1") (pintype "passive"))
      (node (ref "R14") (pin "1") (pinfunction "1_1") (pintype "passive"))
      (node (ref "R15") (pin "1") (pinfunction "1_1") (pintype "passive"))
      (node (ref "SW1") (pin "3") (pinfunction "3_3") (pintype "passive"))
      (node (ref "SW1") (pin "4") (pinfunction "4_4") (pintype "passive"))
      (node (ref "SW2") (pin "3") (pinfunction "3_3") (pintype "passive"))
      (node (ref "SW2") (pin "4") (pinfunction "4_4") (pintype "passive"))
      (node (ref "U1") (pin "1") (pinfunction "GND_01_1") (pintype "passive"))
      (node (ref "U1") (pin "2") (pinfunction "GND_02_2") (pintype "passive"))
      (node (ref "U1") (pin "42") (pinfunction "GND_42") (pintype "passive"))
      (node (ref "U1") (pin "43") (pinfunction "GND_43") (pintype "passive"))
      (node (ref "U1") (pin "46") (pinfunction "GND_46_46") (pintype "passive"))
      (node (ref "U1") (pin "47") (pinfunction "GND_47_47") (pintype "passive"))
      (node (ref "U1") (pin "48") (pinfunction "GND_48_48") (pintype "passive"))
      (node (ref "U1") (pin "49") (pinfunction "GND_49_49") (pintype "passive"))
      (node (ref "U1") (pin "50") (pinfunction "GND_50_50") (pintype "passive"))
      (node (ref "U1") (pin "51") (pinfunction "GND_51_51") (pintype "passive"))
      (node (ref "U1") (pin "52") (pinfunction "GND_52_52") (pintype "passive"))
      (node (ref "U1") (pin "53") (pinfunction "GND_53_53") (pintype "passive"))
      (node (ref "U1") (pin "54") (pinfunction "GND_54_54") (pintype "passive"))
      (node (ref "U1") (pin "55") (pinfunction "GND_55_55") (pintype "passive"))
      (node (ref "U1") (pin "56") (pinfunction "GND_56_56") (pintype "passive"))
      (node (ref "U1") (pin "57") (pinfunction "GND_57_57") (pintype "passive"))
      (node (ref "U1") (pin "58") (pinfunction "GND_58_58") (pintype "passive"))
      (node (ref "U1") (pin "59") (pinfunction "GND_59_59") (pintype "passive"))
      (node (ref "U1") (pin "60") (pinfunction "GND_60_60") (pintype "passive"))
      (node (ref "U1") (pin "61") (pinfunction "GND_61_61") (pintype "passive"))
      (node (ref "U1") (pin "62") (pinfunction "GND_62_62") (pintype "passive"))
      (node (ref "U1") (pin "63") (pinfunction "GND_63_63") (pintype "passive"))
      (node (ref "U1") (pin "64") (pinfunction "GND_64_64") (pintype "passive"))
      (node (ref "U1") (pin "65") (pinfunction "GND_65_65") (pintype "passive"))
      (node (ref "U1") (pin "66") (pinfunction "GND_66_66") (pintype "passive"))
      (node (ref "U1") (pin "67") (pinfunction "GND_67_67") (pintype "passive"))
      (node (ref "U1") (pin "68") (pinfunction "GND_68_68") (pintype "passive"))
      (node (ref "U1") (pin "69") (pinfunction "GND_69_69") (pintype "passive"))
      (node (ref "U1") (pin "70") (pinfunction "GND_70_70") (pintype "passive"))
      (node (ref "U1") (pin "71") (pinfunction "GND_71_71") (pintype "passive"))
      (node (ref "U1") (pin "72") (pinfunction "GND_72_72") (pintype "passive"))
      (node (ref "U1") (pin "73") (pinfunction "GND_73_73") (pintype "passive"))
      (node (ref "U2") (pin "13") (pinfunction "GND_13") (pintype "passive"))
      (node (ref "U2") (pin "21") (pinfunction "GND_21") (pintype "passive"))
      (node (ref "U2") (pin "3") (pinfunction "GND_3") (pintype "passive"))
      (node (ref "U3") (pin "2") (pinfunction "GND_2") (pintype "power_in"))
      (node (ref "U3") (pin "4") (pinfunction "GND_4") (pintype "power_in"))
    )
    (net (code "64") (name "Net-(D1-Pad2)") (class "Default")
      (node (ref "D1") (pin "2") (pinfunction "2_2") (pintype "passive"))
      (node (ref "R5") (pin "1") (pinfunction "1_1") (pintype "passive"))
    )
    (net (code "65") (name "Net-(D2-Pad2)") (class "Default")
      (node (ref "D2") (pin "2") (pinfunction "2_2") (pintype "passive"))
      (node (ref "R4") (pin "1") (pinfunction "1_1") (pintype "passive"))
    )
    (net (code "66") (name "Net-(J3-CC1)") (class "Default")
      (node (ref "J3") (pin "A5") (pinfunction "CC1_A5") (pintype "passive"))
      (node (ref "R12") (pin "2") (pinfunction "2_2") (pintype "passive"))
    )
    (net (code "67") (name "Net-(J3-CC2)") (class "Default")
      (node (ref "J3") (pin "B5") (pinfunction "CC2_B5") (pintype "passive"))
      (node (ref "R11") (pin "2") (pinfunction "2_2") (pintype "passive"))
    )
    (net (code "68") (name "Net-(J3-DP1)") (class "Default")
      (node (ref "D5") (pin "2") (pinfunction "2_2") (pintype "passive"))
      (node (ref "J3") (pin "A6") (pinfunction "DP1_A6") (pintype "passive"))
      (node (ref "J3") (pin "B6") (pinfunction "DP2_B6") (pintype "passive"))
      (node (ref "R7") (pin "1") (pinfunction "1_1") (pintype "passive"))
    )
    (net (code "69") (name "Net-(J4-CC1)") (class "Default")
      (node (ref "J4") (pin "A5") (pinfunction "CC1_A5") (pintype "passive"))
      (node (ref "R15") (pin "2") (pinfunction "2_2") (pintype "passive"))
    )
    (net (code "70") (name "Net-(J4-CC2)") (class "Default")
      (node (ref "J4") (pin "B5") (pinfunction "CC2_B5") (pintype "passive"))
      (node (ref "R14") (pin "2") (pinfunction "2_2") (pintype "passive"))
    )
    (net (code "71") (name "Net-(Q1-B)") (class "Default")
      (node (ref "Q1") (pin "1") (pinfunction "B_1") (pintype "passive"))
      (node (ref "R18") (pin "1") (pinfunction "1_1") (pintype "passive"))
    )
    (net (code "72") (name "Net-(Q2-B)") (class "Default")
      (node (ref "Q2") (pin "1") (pinfunction "B_1") (pintype "passive"))
      (node (ref "R22") (pin "1") (pinfunction "1_1") (pintype "passive"))
    )
    (net (code "73") (name "Net-(U2-CBUS0)") (class "Default")
      (node (ref "R10") (pin "1") (pinfunction "1_1") (pintype "passive"))
      (node (ref "U2") (pin "15") (pinfunction "CBUS0_15") (pintype "passive"))
    )
    (net (code "74") (name "Net-(U2-~{RESET})") (class "Default")
      (node (ref "C7") (pin "1") (pinfunction "1_1") (pintype "passive"))
      (node (ref "R8") (pin "2") (pinfunction "2_2") (pintype "passive"))
      (node (ref "U2") (pin "11") (pinfunction "~{RESET}_11") (pintype "passive"))
    )
    (net (code "75") (name "unconnected-(J1-Pad24)") (class "Default")
      (node (ref "J1") (pin "24") (pinfunction "24_24") (pintype "passive+no_connect"))
    )
    (net (code "76") (name "unconnected-(J3-SBU1-PadA8)") (class "Default")
      (node (ref "J3") (pin "A8") (pinfunction "SBU1_A8") (pintype "passive+no_connect"))
    )
    (net (code "77") (name "unconnected-(J3-SBU2-PadB8)") (class "Default")
      (node (ref "J3") (pin "B8") (pinfunction "SBU2_B8") (pintype "passive+no_connect"))
    )
    (net (code "78") (name "unconnected-(J4-SBU1-PadA8)") (class "Default")
      (node (ref "J4") (pin "A8") (pinfunction "SBU1_A8") (pintype "passive+no_connect"))
    )
    (net (code "79") (name "unconnected-(J4-SBU2-PadB8)") (class "Default")
      (node (ref "J4") (pin "B8") (pinfunction "SBU2_B8") (pintype "passive+no_connect"))
    )
    (net (code "80") (name "unconnected-(U2-CBUS1-Pad14)") (class "Default")
      (node (ref "U2") (pin "14") (pinfunction "CBUS1_14") (pintype "passive+no_connect"))
    )
    (net (code "81") (name "unconnected-(U2-CBUS2-Pad7)") (class "Default")
      (node (ref "U2") (pin "7") (pinfunction "CBUS2_7") (pintype "passive+no_connect"))
    )
    (net (code "82") (name "unconnected-(U2-~{CTS}-Pad6)") (class "Default")
      (node (ref "U2") (pin "6") (pinfunction "~{CTS}_6") (pintype "passive+no_connect"))
    )
    (net (code "83") (name "unconnected-(U2-~{DCD}-Pad5)") (class "Default")
      (node (ref "U2") (pin "5") (pinfunction "~{DCD}_5") (pintype "passive+no_connect"))
    )
    (net (code "84") (name "unconnected-(U2-~{DSR}-Pad4)") (class "Default")
      (node (ref "U2") (pin "4") (pinfunction "~{DSR}_4") (pintype "passive+no_connect"))
    )
    (net (code "85") (name "unconnected-(U2-~{RI}-Pad2)") (class "Default")
      (node (ref "U2") (pin "2") (pinfunction "~{RI}_2") (pintype "passive+no_connect"))
    )
  )
)
